# femto-beacon-esp32coin.net
KiCad netlist of a schematic drawn in EAGLE
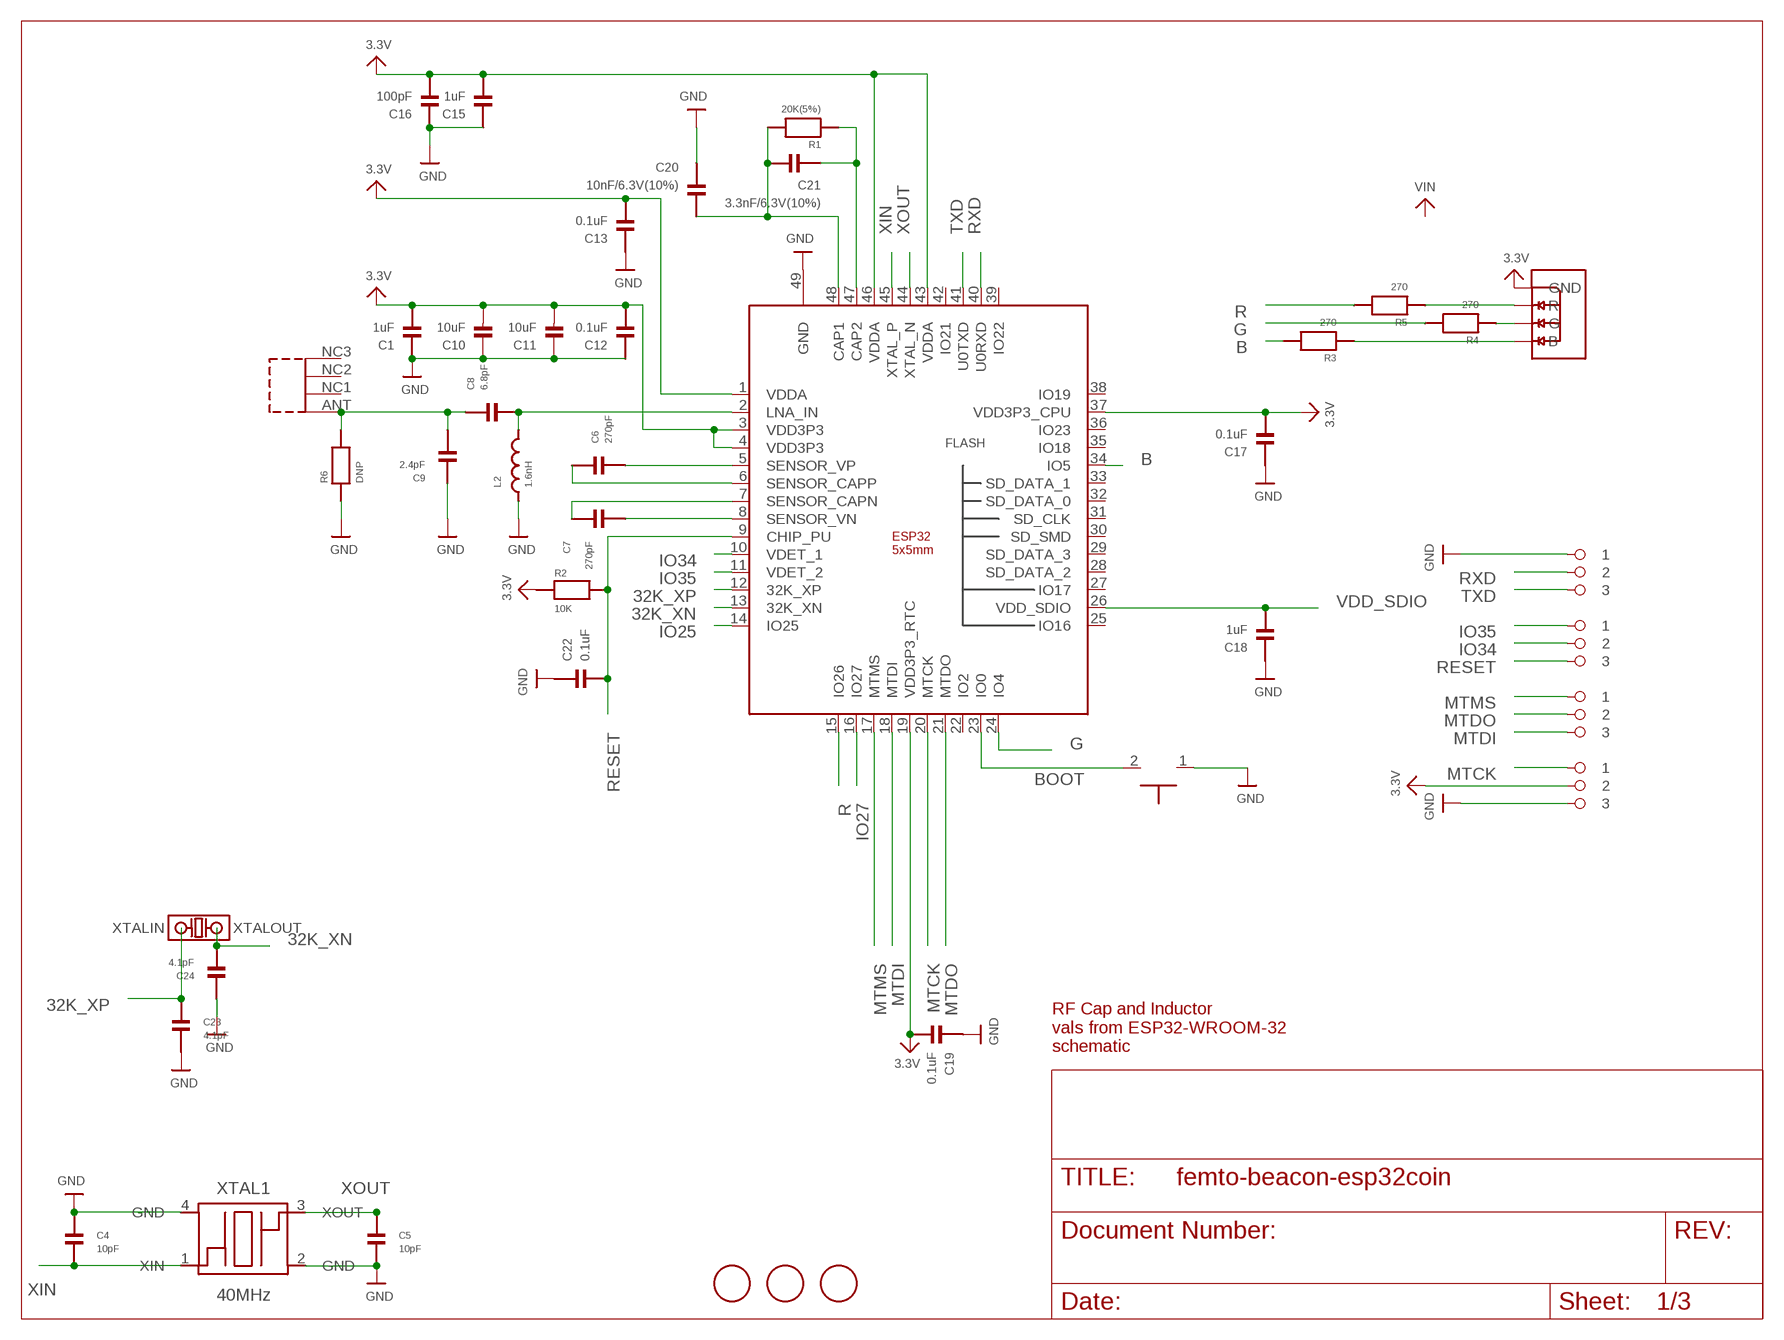
[diagram p0: schematic, sheet 1]
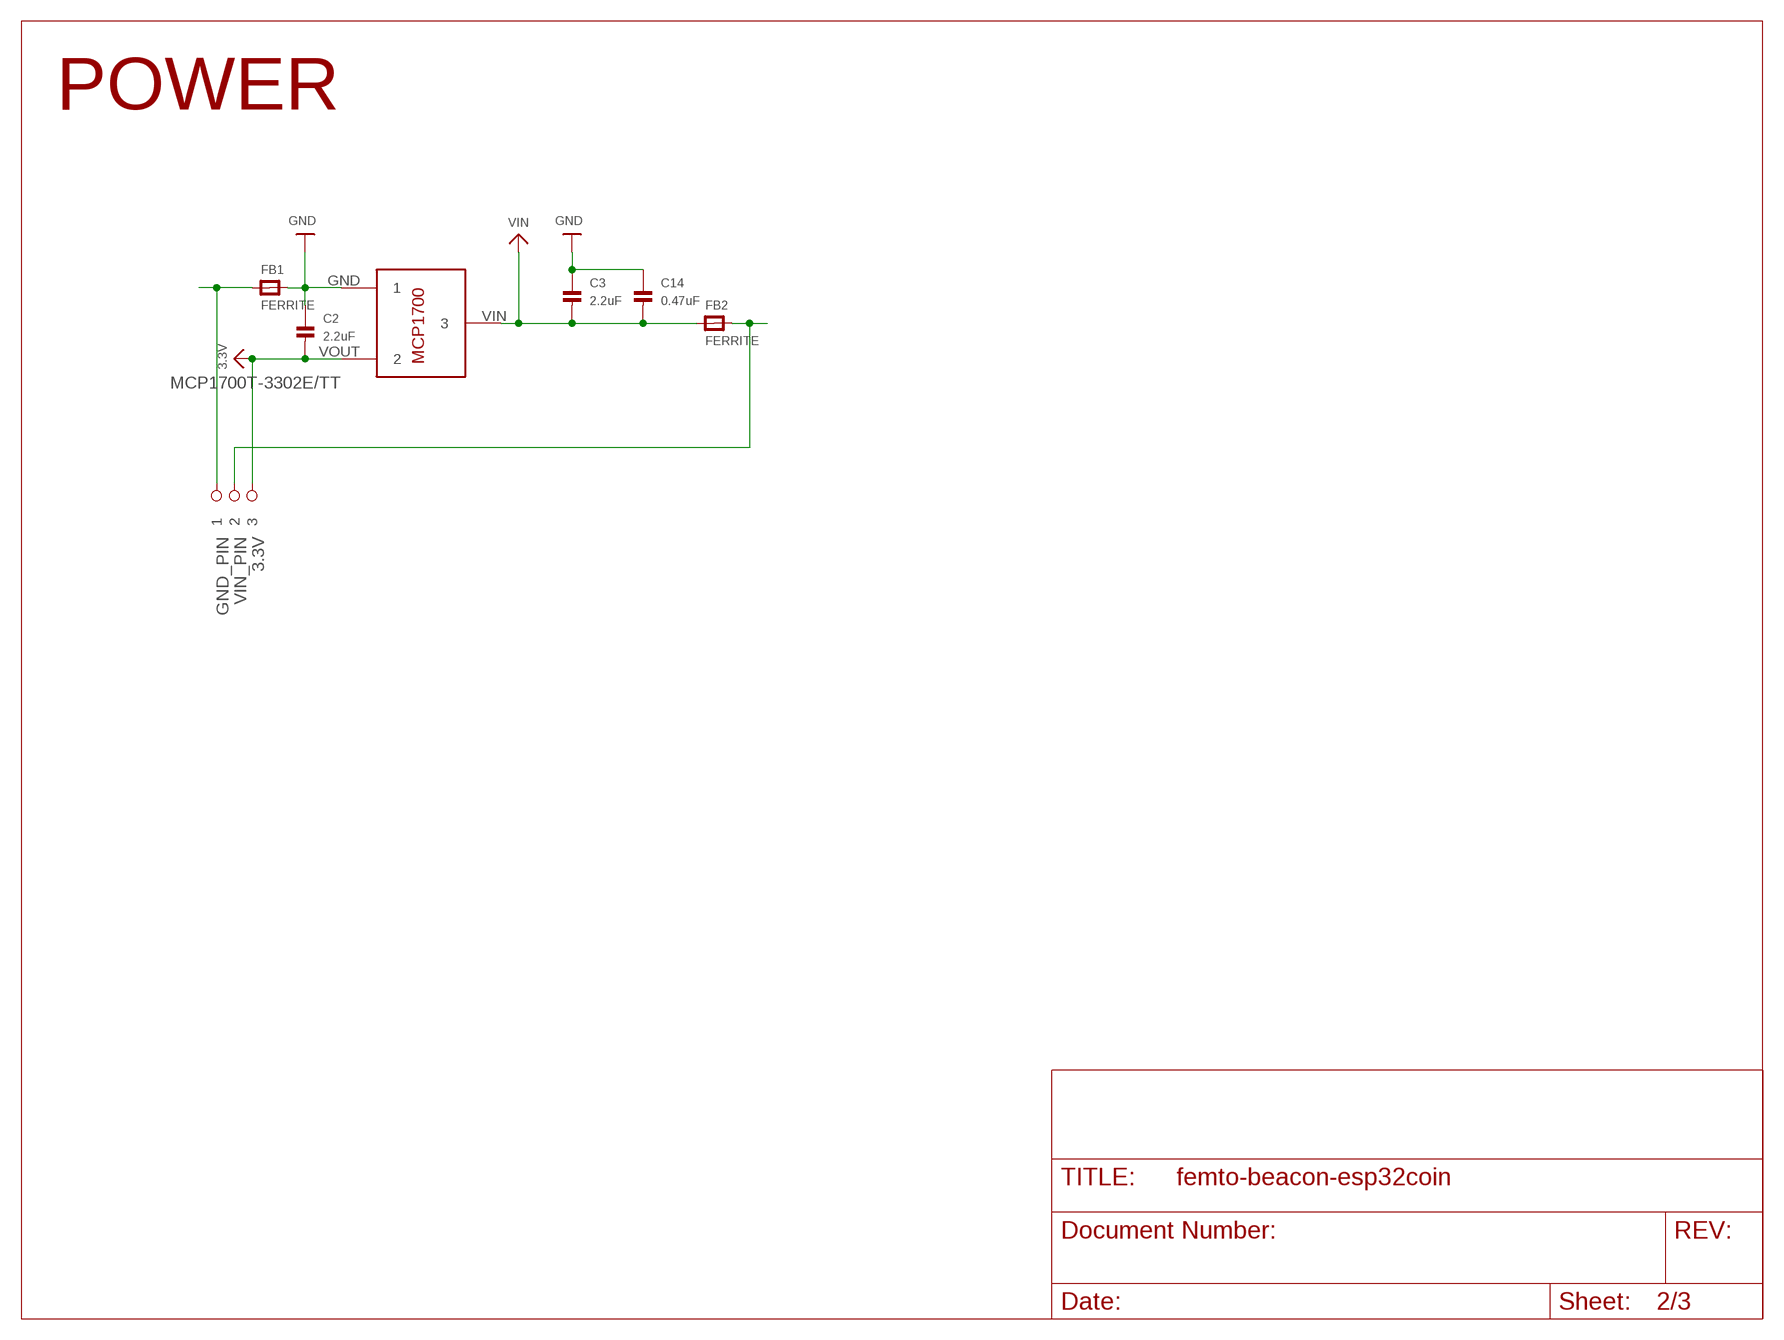
[diagram p1: schematic, sheet 2]
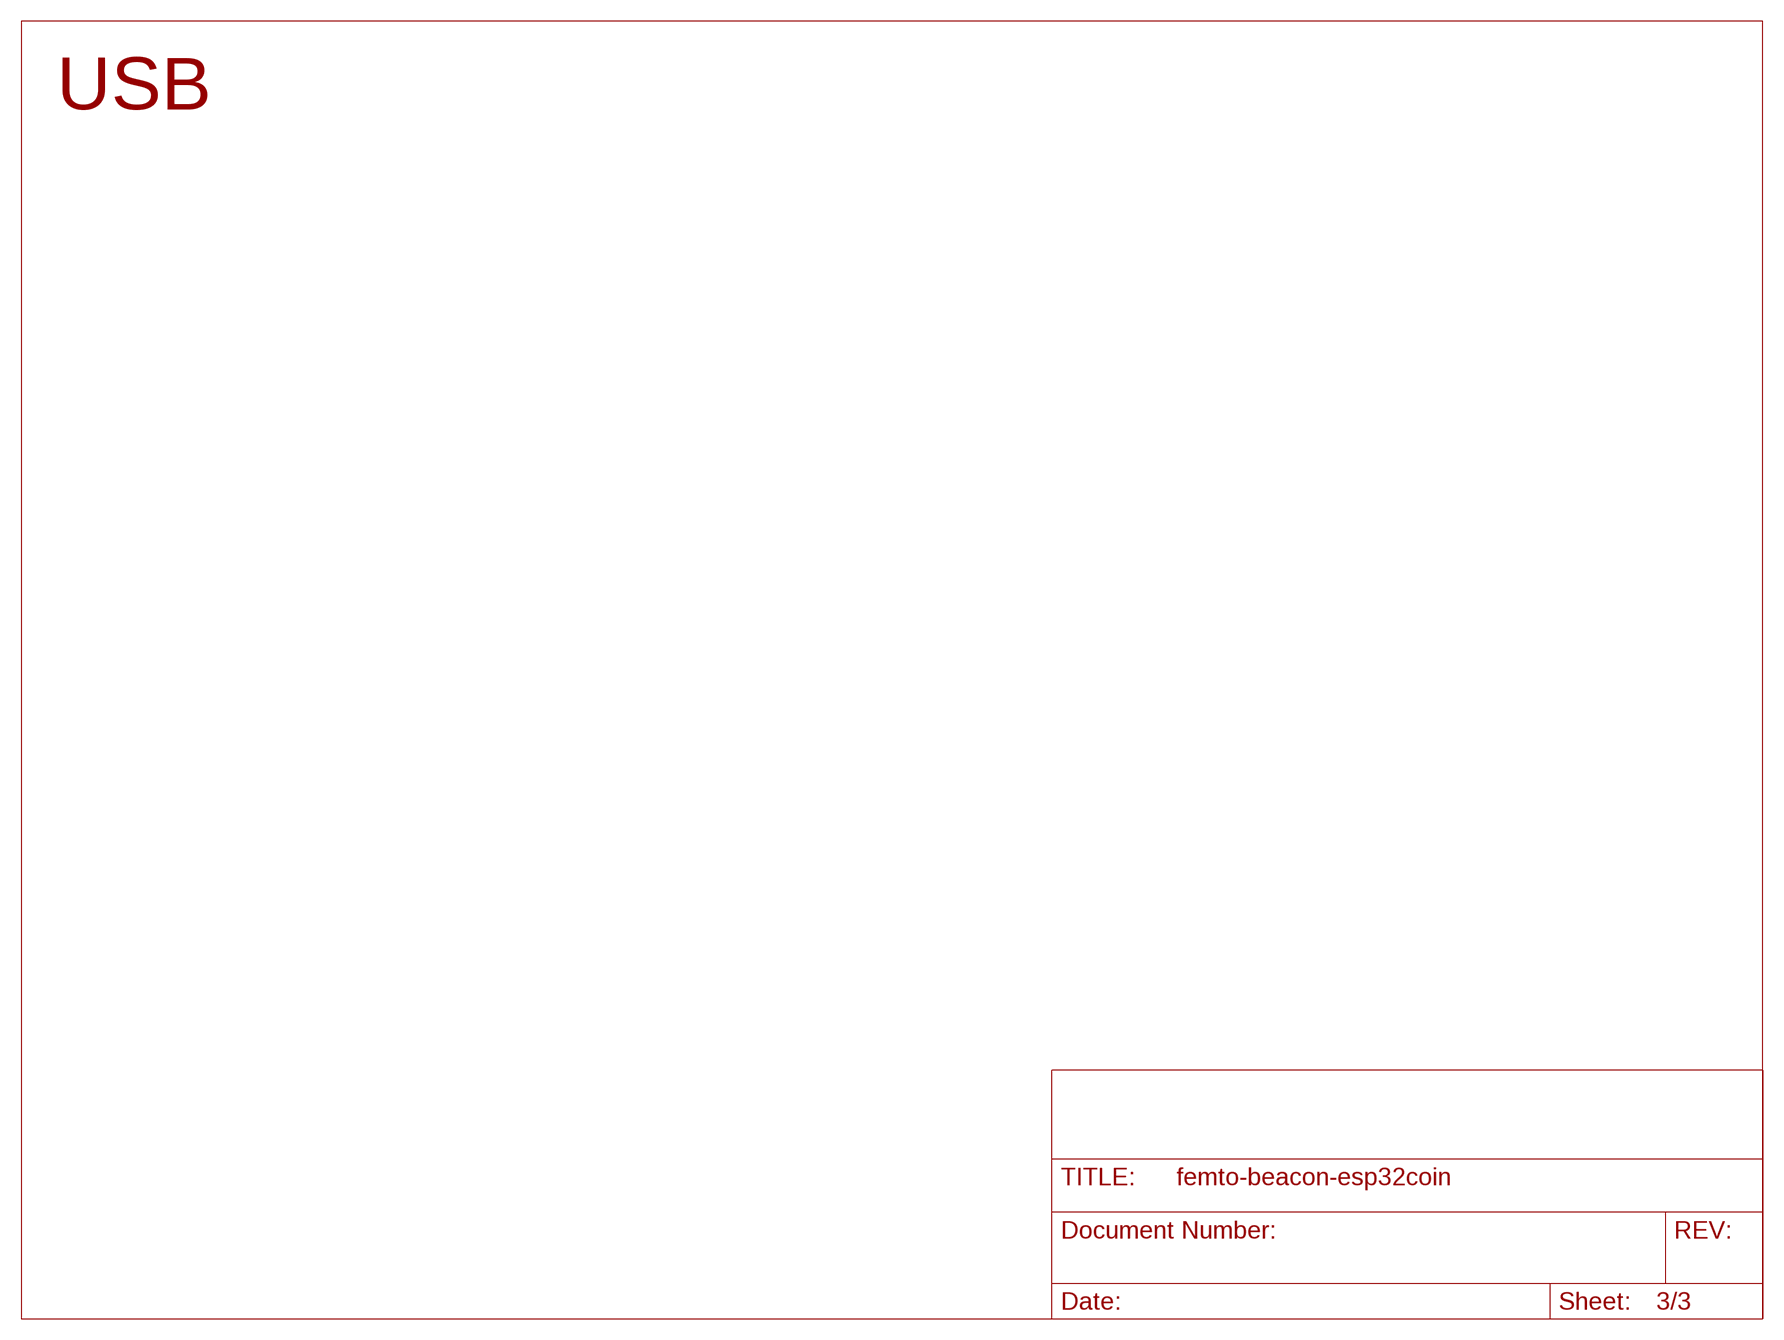
[diagram p2: schematic, sheet 3]

(export (version "E")
  (design (tool "Eeschema 10.0.6"))
  (components
    (comp (ref "C2")
      (value "2.2uF")
      (footprint "eagle-import:_0402MP")
      (fields (field (name "MPN") "C1005X5R0J225K050BC"))
      (libsource (lib "eagle-import") (part "CAP_CERAMIC_0402MP"))
    )
    (comp (ref "C3")
      (value "2.2uF")
      (footprint "eagle-import:_0402MP")
      (fields (field (name "MPN") "C1005X5R0J225K050BC"))
      (libsource (lib "eagle-import") (part "CAP_CERAMIC_0402MP"))
    )
    (comp (ref "C14")
      (value "0.47uF")
      (footprint "eagle-import:_0402MP")
      (fields (field (name "MPN") "GRM155R60J474KE19D"))
      (libsource (lib "eagle-import") (part "CAP_CERAMIC_0402MP"))
    )
    (comp (ref "FB1")
      (value "FERRITE")
      (footprint "eagle-import:_0603MP")
      (fields (field (name "MPN") "BLM18RK102SN1D"))
      (libsource (lib "eagle-import") (part "FERRITE_0603MP"))
    )
    (comp (ref "FB2")
      (value "FERRITE")
      (footprint "eagle-import:_0603MP")
      (fields (field (name "MPN") "BLM18RK102SN1D"))
      (libsource (lib "eagle-import") (part "FERRITE_0603MP"))
    )
    (comp (ref "LDO1")
      (value "MCP1700T-3302E/TT")
      (footprint "eagle-import:MCP1700T-3302E_TT")
      (libsource (lib "eagle-import") (part "MCP1700T-3302E/TT"))
    )
    (comp (ref "PIN_PWR")
      (value "1X3_ROUND")
      (footprint "eagle-import:1X3_ROUND")
      (libsource (lib "eagle-import") (part "1X3_ROUND"))
    )
    (comp (ref "ANT1")
      (value "0479480001")
      (footprint "eagle-import:0479480001")
      (libsource (lib "eagle-import") (part "0479480001"))
    )
    (comp (ref "BOOT1")
      (value "TACTILE_SWITCH_NO_GND_NO_BOSS")
      (footprint "eagle-import:SIDE_ACT_NO_GND_NO_BOSS")
      (fields (field (name "MPN") "B3U-3000P"))
      (libsource (lib "eagle-import") (part "TACTILE_SWITCH_NO_GND_NO_BOSS"))
    )
    (comp (ref "C1")
      (value "1uF")
      (footprint "eagle-import:PART")
      (fields (field (name "MPN") "CL03A105KQ3CSNH"))
      (libsource (lib "eagle-import") (part "CAPACITOR_0201"))
    )
    (comp (ref "C4")
      (value "10pF")
      (footprint "eagle-import:PART")
      (fields (field (name "MPN") "02013A100JAT2A"))
      (libsource (lib "eagle-import") (part "CAPACITOR_0201"))
    )
    (comp (ref "C5")
      (value "10pF")
      (footprint "eagle-import:PART")
      (fields (field (name "MPN") "02013A100JAT2A"))
      (libsource (lib "eagle-import") (part "CAPACITOR_0201"))
    )
    (comp (ref "C6")
      (value "270pF")
      (footprint "eagle-import:PART")
      (fields (field (name "MPN") "GRM033R71C271KA01D"))
      (libsource (lib "eagle-import") (part "CAPACITOR_0201"))
    )
    (comp (ref "C7")
      (value "270pF")
      (footprint "eagle-import:PART")
      (fields (field (name "MPN") "GRM033R71C271KA01D"))
      (libsource (lib "eagle-import") (part "CAPACITOR_0201"))
    )
    (comp (ref "C8")
      (value "6.8pF")
      (footprint "eagle-import:PART")
      (fields (field (name "MPN") "GRM0335C2A6R8DA01D"))
      (libsource (lib "eagle-import") (part "CAPACITOR_0201"))
    )
    (comp (ref "C9")
      (value "2.4pF")
      (footprint "eagle-import:PART")
      (fields (field (name "MPN") "GRM0335C1H2R4CA01D"))
      (libsource (lib "eagle-import") (part "CAPACITOR_0201"))
    )
    (comp (ref "C10")
      (value "10uF")
      (footprint "eagle-import:_0603MP")
      (fields (field (name "MPN") "GRM188R61C106KAALD"))
      (libsource (lib "eagle-import") (part "CAP_CERAMIC_0603MP"))
    )
    (comp (ref "C11")
      (value "10uF")
      (footprint "eagle-import:_0603MP")
      (fields (field (name "MPN") "GRM188R61C106KAALD"))
      (libsource (lib "eagle-import") (part "CAP_CERAMIC_0603MP"))
    )
    (comp (ref "C12")
      (value "0.1uF")
      (footprint "eagle-import:PART")
      (fields (field (name "MPN") "GRM033C80J104KE84D"))
      (libsource (lib "eagle-import") (part "CAPACITOR_0201"))
    )
    (comp (ref "C13")
      (value "0.1uF")
      (footprint "eagle-import:PART")
      (fields (field (name "MPN") "GRM033C80J104KE84D"))
      (libsource (lib "eagle-import") (part "CAPACITOR_0201"))
    )
    (comp (ref "C15")
      (value "1uF")
      (footprint "eagle-import:PART")
      (fields (field (name "MPN") "CL03A105KQ3CSNH"))
      (libsource (lib "eagle-import") (part "CAPACITOR_0201"))
    )
    (comp (ref "C16")
      (value "100pF")
      (footprint "eagle-import:PART")
      (fields (field (name "MPN") "0201YC101KAT2A"))
      (libsource (lib "eagle-import") (part "CAPACITOR_0201"))
    )
    (comp (ref "C17")
      (value "0.1uF")
      (footprint "eagle-import:PART")
      (fields (field (name "MPN") "GRM033C80J104KE84D"))
      (libsource (lib "eagle-import") (part "CAPACITOR_0201"))
    )
    (comp (ref "C18")
      (value "1uF")
      (footprint "eagle-import:PART")
      (fields (field (name "MPN") "CL03A105KQ3CSNH"))
      (libsource (lib "eagle-import") (part "CAPACITOR_0201"))
    )
    (comp (ref "C19")
      (value "0.1uF")
      (footprint "eagle-import:PART")
      (fields (field (name "MPN") "GRM033C80J104KE84D"))
      (libsource (lib "eagle-import") (part "CAPACITOR_0201"))
    )
    (comp (ref "C20")
      (value "10nF/6.3V(10%)")
      (footprint "eagle-import:PART")
      (fields (field (name "MPN") "GRM033R70J103KA01D"))
      (libsource (lib "eagle-import") (part "CAPACITOR_0201"))
    )
    (comp (ref "C21")
      (value "3.3nF/6.3V(10%)")
      (footprint "eagle-import:PART")
      (fields (field (name "MPN") "GRM033R70J332KA01D"))
      (libsource (lib "eagle-import") (part "CAPACITOR_0201"))
    )
    (comp (ref "C22")
      (value "0.1uF")
      (footprint "eagle-import:PART")
      (fields (field (name "MPN") "GRM033C80J104KE84D"))
      (libsource (lib "eagle-import") (part "CAPACITOR_0201"))
    )
    (comp (ref "C23")
      (value "4.1pF")
      (footprint "eagle-import:PART")
      (fields (field (name "MPN") "GRM0335C1H4R1BA01D"))
      (libsource (lib "eagle-import") (part "CAPACITOR_0201"))
    )
    (comp (ref "C24")
      (value "4.1pF")
      (footprint "eagle-import:PART")
      (fields (field (name "MPN") "GRM0335C1H4R1BA01D"))
      (libsource (lib "eagle-import") (part "CAPACITOR_0201"))
    )
    (comp (ref "FID1")
      (value "FIDUCIAL")
      (footprint "eagle-import:FIDUCIAL_1MM")
      (libsource (lib "eagle-import") (part "FIDUCIAL"))
    )
    (comp (ref "FID2")
      (value "FIDUCIAL")
      (footprint "eagle-import:FIDUCIAL_1MM")
      (libsource (lib "eagle-import") (part "FIDUCIAL"))
    )
    (comp (ref "FID3")
      (value "FIDUCIAL")
      (footprint "eagle-import:FIDUCIAL_1MM")
      (libsource (lib "eagle-import") (part "FIDUCIAL"))
    )
    (comp (ref "IC1")
      (value "ESP32-QFN_5X5")
      (footprint "eagle-import:ESP32-QFN48_5X5")
      (fields (field (name "MPN") "ESP32-D2WD"))
      (libsource (lib "eagle-import") (part "ESP32-QFN_5X5"))
    )
    (comp (ref "L2")
      (value "1.6nH")
      (footprint "eagle-import:PART")
      (fields (field (name "MPN") "LQP03HQ1N6B02D"))
      (libsource (lib "eagle-import") (part "INDUCTOR_FIXED_0201"))
    )
    (comp (ref "PIN_EN")
      (value "1X3_ROUND")
      (footprint "eagle-import:1X3_ROUND")
      (libsource (lib "eagle-import") (part "1X3_ROUND"))
    )
    (comp (ref "PIN_GPIO_A")
      (value "1X3_ROUND")
      (footprint "eagle-import:1X3_ROUND")
      (libsource (lib "eagle-import") (part "1X3_ROUND"))
    )
    (comp (ref "PIN_GPIO_B")
      (value "1X3_ROUND")
      (footprint "eagle-import:1X3_ROUND")
      (libsource (lib "eagle-import") (part "1X3_ROUND"))
    )
    (comp (ref "PIN_UART")
      (value "1X3_ROUND")
      (footprint "eagle-import:1X3_ROUND")
      (libsource (lib "eagle-import") (part "1X3_ROUND"))
    )
    (comp (ref "R1")
      (value "20K(5%)")
      (footprint "eagle-import:PART")
      (fields (field (name "MPN") "RC0201JR-0720KL"))
      (libsource (lib "eagle-import") (part "RESISTOR_0201"))
    )
    (comp (ref "R2")
      (value "10K")
      (footprint "eagle-import:PART")
      (fields (field (name "MPN") "RC0201JR-0710KL"))
      (libsource (lib "eagle-import") (part "RESISTOR_0201"))
    )
    (comp (ref "R3")
      (value "270")
      (footprint "eagle-import:PART")
      (fields (field (name "MPN") "RC0201FR-07270RL"))
      (libsource (lib "eagle-import") (part "RESISTOR_0201"))
    )
    (comp (ref "R4")
      (value "270")
      (footprint "eagle-import:PART")
      (fields (field (name "MPN") "RC0201FR-07270RL"))
      (libsource (lib "eagle-import") (part "RESISTOR_0201"))
    )
    (comp (ref "R5")
      (value "270")
      (footprint "eagle-import:PART")
      (fields (field (name "MPN") "RC0201FR-07270RL"))
      (libsource (lib "eagle-import") (part "RESISTOR_0201"))
    )
    (comp (ref "R6")
      (value "DNP")
      (footprint "eagle-import:PART")
      (libsource (lib "eagle-import") (part "RESISTOR_0201"))
    )
    (comp (ref "RGB1")
      (value "LRTB_R48G")
      (footprint "eagle-import:LRTB_R48G")
      (fields (field (name "MPN") "LRTB R48G"))
      (libsource (lib "eagle-import") (part "LRTB_R48G"))
    )
    (comp (ref "XTAL1")
      (value "40MHz")
      (footprint "eagle-import:FA-128")
      (fields (field (name "MPN") "FA-128 40.0000MF10Z-K3"))
      (libsource (lib "eagle-import") (part "FA-128"))
    )
    (comp (ref "XTAL2")
      (value "ABS06-107-32.768KHZ-T")
      (footprint "eagle-import:ABS06-107-32.768KHZ-T")
      (fields (field (name "MPN") "ABS06-107-32.768kHz-T"))
      (libsource (lib "eagle-import") (part "ABS06-107-32.768KHZ-T"))
    )
  )
  (nets
    (net (code "1") (name "3.3V") (class "Default")
      (node (ref "C1") (pin "2") (pinfunction "P$2_2") (pintype "bidirectional"))
      (node (ref "C10") (pin "2") (pinfunction "P$2_2") (pintype "passive"))
      (node (ref "C11") (pin "2") (pinfunction "P$2_2") (pintype "passive"))
      (node (ref "C12") (pin "2") (pinfunction "P$2_2") (pintype "bidirectional"))
      (node (ref "C13") (pin "2") (pinfunction "P$2_2") (pintype "bidirectional"))
      (node (ref "C15") (pin "2") (pinfunction "P$2_2") (pintype "bidirectional"))
      (node (ref "C16") (pin "2") (pinfunction "P$2_2") (pintype "bidirectional"))
      (node (ref "C17") (pin "2") (pinfunction "P$2_2") (pintype "bidirectional"))
      (node (ref "C19") (pin "2") (pinfunction "P$2_2") (pintype "bidirectional"))
      (node (ref "C2") (pin "2") (pinfunction "P$2_2") (pintype "passive"))
      (node (ref "IC1") (pin "1") (pinfunction "VDDA_1") (pintype "power_in"))
      (node (ref "IC1") (pin "19") (pinfunction "VDD3P3_RTC_19") (pintype "power_in"))
      (node (ref "IC1") (pin "3") (pinfunction "VDD3P3_3") (pintype "power_in"))
      (node (ref "IC1") (pin "37") (pinfunction "VDD3P3_CPU_37") (pintype "power_in"))
      (node (ref "IC1") (pin "4") (pinfunction "VDD3P3_4") (pintype "power_in"))
      (node (ref "IC1") (pin "43") (pinfunction "VDDA_43") (pintype "power_in"))
      (node (ref "IC1") (pin "46") (pinfunction "VDDA_46") (pintype "power_in"))
      (node (ref "LDO1") (pin "VOUT") (pinfunction "2_VOUT") (pintype "bidirectional"))
      (node (ref "PIN_GPIO_A") (pin "P$2") (pinfunction "2_P$2") (pintype "bidirectional"))
      (node (ref "PIN_PWR") (pin "P$3") (pinfunction "3_P$3") (pintype "bidirectional"))
      (node (ref "R2") (pin "1") (pinfunction "1_1") (pintype "bidirectional"))
      (node (ref "RGB1") (pin "1") (pinfunction "GND_1") (pintype "bidirectional"))
    )
    (net (code "2") (name "32K_XN") (class "Default")
      (node (ref "C24") (pin "1") (pinfunction "P$1_1") (pintype "bidirectional"))
      (node (ref "IC1") (pin "13") (pinfunction "32K_XN_13") (pintype "bidirectional"))
      (node (ref "XTAL2") (pin "2") (pinfunction "XTALOUT_2") (pintype "bidirectional"))
    )
    (net (code "3") (name "32K_XP") (class "Default")
      (node (ref "C23") (pin "2") (pinfunction "P$2_2") (pintype "bidirectional"))
      (node (ref "IC1") (pin "12") (pinfunction "32K_XP_12") (pintype "bidirectional"))
      (node (ref "XTAL2") (pin "1") (pinfunction "XTALIN_1") (pintype "bidirectional"))
    )
    (net (code "4") (name "B") (class "Default")
      (node (ref "IC1") (pin "34") (pinfunction "IO5_34") (pintype "bidirectional"))
      (node (ref "R3") (pin "2") (pinfunction "2_2") (pintype "bidirectional"))
    )
    (net (code "5") (name "BOOT") (class "Default")
      (node (ref "BOOT1") (pin "2") (pinfunction "2_2") (pintype "bidirectional"))
      (node (ref "IC1") (pin "23") (pinfunction "IO0_23") (pintype "bidirectional"))
    )
    (net (code "6") (name "G") (class "Default")
      (node (ref "IC1") (pin "24") (pinfunction "IO4_24") (pintype "bidirectional"))
      (node (ref "R4") (pin "2") (pinfunction "2_2") (pintype "bidirectional"))
    )
    (net (code "7") (name "GND") (class "Default")
      (node (ref "BOOT1") (pin "1") (pinfunction "1_1") (pintype "bidirectional"))
      (node (ref "C1") (pin "1") (pinfunction "P$1_1") (pintype "bidirectional"))
      (node (ref "C10") (pin "1") (pinfunction "P$1_1") (pintype "passive"))
      (node (ref "C11") (pin "1") (pinfunction "P$1_1") (pintype "passive"))
      (node (ref "C12") (pin "1") (pinfunction "P$1_1") (pintype "bidirectional"))
      (node (ref "C13") (pin "1") (pinfunction "P$1_1") (pintype "bidirectional"))
      (node (ref "C14") (pin "1") (pinfunction "P$1_1") (pintype "passive"))
      (node (ref "C15") (pin "1") (pinfunction "P$1_1") (pintype "bidirectional"))
      (node (ref "C16") (pin "1") (pinfunction "P$1_1") (pintype "bidirectional"))
      (node (ref "C17") (pin "1") (pinfunction "P$1_1") (pintype "bidirectional"))
      (node (ref "C18") (pin "1") (pinfunction "P$1_1") (pintype "bidirectional"))
      (node (ref "C19") (pin "1") (pinfunction "P$1_1") (pintype "bidirectional"))
      (node (ref "C2") (pin "1") (pinfunction "P$1_1") (pintype "passive"))
      (node (ref "C20") (pin "1") (pinfunction "P$1_1") (pintype "bidirectional"))
      (node (ref "C22") (pin "1") (pinfunction "P$1_1") (pintype "bidirectional"))
      (node (ref "C23") (pin "1") (pinfunction "P$1_1") (pintype "bidirectional"))
      (node (ref "C24") (pin "2") (pinfunction "P$2_2") (pintype "bidirectional"))
      (node (ref "C3") (pin "1") (pinfunction "P$1_1") (pintype "passive"))
      (node (ref "C4") (pin "1") (pinfunction "P$1_1") (pintype "bidirectional"))
      (node (ref "C5") (pin "1") (pinfunction "P$1_1") (pintype "bidirectional"))
      (node (ref "C9") (pin "1") (pinfunction "P$1_1") (pintype "bidirectional"))
      (node (ref "FB1") (pin "2") (pinfunction "P$2_2") (pintype "passive"))
      (node (ref "IC1") (pin "49") (pinfunction "GND_49") (pintype "power_in"))
      (node (ref "L2") (pin "1") (pinfunction "P$1_1") (pintype "bidirectional"))
      (node (ref "LDO1") (pin "GND") (pinfunction "1_GND") (pintype "bidirectional"))
      (node (ref "PIN_GPIO_A") (pin "P$3") (pinfunction "3_P$3") (pintype "bidirectional"))
      (node (ref "PIN_UART") (pin "P$1") (pinfunction "1_P$1") (pintype "bidirectional"))
      (node (ref "R6") (pin "1") (pinfunction "1_1") (pintype "bidirectional"))
      (node (ref "XTAL1") (pin "2") (pinfunction "GND_2") (pintype "bidirectional"))
      (node (ref "XTAL1") (pin "4") (pinfunction "GND_4") (pintype "bidirectional"))
    )
    (net (code "8") (name "GND_PIN") (class "Default")
      (node (ref "FB1") (pin "1") (pinfunction "P$1_1") (pintype "passive"))
      (node (ref "PIN_PWR") (pin "P$1") (pinfunction "1_P$1") (pintype "bidirectional"))
    )
    (net (code "9") (name "IO25") (class "Default")
      (node (ref "IC1") (pin "14") (pinfunction "IO25_14") (pintype "bidirectional"))
    )
    (net (code "10") (name "IO27") (class "Default")
      (node (ref "IC1") (pin "16") (pinfunction "IO27_16") (pintype "bidirectional"))
    )
    (net (code "11") (name "IO34") (class "Default")
      (node (ref "IC1") (pin "10") (pinfunction "VDET_1_10") (pintype "input"))
      (node (ref "PIN_EN") (pin "P$2") (pinfunction "2_P$2") (pintype "bidirectional"))
    )
    (net (code "12") (name "IO35") (class "Default")
      (node (ref "IC1") (pin "11") (pinfunction "VDET_2_11") (pintype "input"))
      (node (ref "PIN_EN") (pin "P$1") (pinfunction "1_P$1") (pintype "bidirectional"))
    )
    (net (code "13") (name "MTCK") (class "Default")
      (node (ref "IC1") (pin "20") (pinfunction "MTCK_20") (pintype "bidirectional"))
      (node (ref "PIN_GPIO_A") (pin "P$1") (pinfunction "1_P$1") (pintype "bidirectional"))
    )
    (net (code "14") (name "MTDI") (class "Default")
      (node (ref "IC1") (pin "18") (pinfunction "MTDI_18") (pintype "bidirectional"))
      (node (ref "PIN_GPIO_B") (pin "P$3") (pinfunction "3_P$3") (pintype "bidirectional"))
    )
    (net (code "15") (name "MTDO") (class "Default")
      (node (ref "IC1") (pin "21") (pinfunction "MTDO_21") (pintype "bidirectional"))
      (node (ref "PIN_GPIO_B") (pin "P$2") (pinfunction "2_P$2") (pintype "bidirectional"))
    )
    (net (code "16") (name "MTMS") (class "Default")
      (node (ref "IC1") (pin "17") (pinfunction "MTMS_17") (pintype "bidirectional"))
      (node (ref "PIN_GPIO_B") (pin "P$1") (pinfunction "1_P$1") (pintype "bidirectional"))
    )
    (net (code "17") (name "Net-(ANT1-1)") (class "Default")
      (node (ref "ANT1") (pin "ANT") (pinfunction "1_ANT") (pintype "bidirectional"))
      (node (ref "C8") (pin "1") (pinfunction "P$1_1") (pintype "bidirectional"))
      (node (ref "C9") (pin "2") (pinfunction "P$2_2") (pintype "bidirectional"))
      (node (ref "R6") (pin "2") (pinfunction "2_2") (pintype "bidirectional"))
    )
    (net (code "18") (name "Net-(C6-P$1)") (class "Default")
      (node (ref "C6") (pin "1") (pinfunction "P$1_1") (pintype "bidirectional"))
      (node (ref "IC1") (pin "5") (pinfunction "SENSOR_VP_5") (pintype "input"))
    )
    (net (code "19") (name "Net-(C6-P$2)") (class "Default")
      (node (ref "C6") (pin "2") (pinfunction "P$2_2") (pintype "bidirectional"))
      (node (ref "IC1") (pin "6") (pinfunction "SENSOR_CAPP_6") (pintype "input"))
    )
    (net (code "20") (name "Net-(C7-P$1)") (class "Default")
      (node (ref "C7") (pin "1") (pinfunction "P$1_1") (pintype "bidirectional"))
      (node (ref "IC1") (pin "7") (pinfunction "SENSOR_CAPN_7") (pintype "input"))
    )
    (net (code "21") (name "Net-(C7-P$2)") (class "Default")
      (node (ref "C7") (pin "2") (pinfunction "P$2_2") (pintype "bidirectional"))
      (node (ref "IC1") (pin "8") (pinfunction "SENSOR_VN_8") (pintype "input"))
    )
    (net (code "22") (name "Net-(C8-P$2)") (class "Default")
      (node (ref "C8") (pin "2") (pinfunction "P$2_2") (pintype "bidirectional"))
      (node (ref "IC1") (pin "2") (pinfunction "LNA_IN_2") (pintype "bidirectional"))
      (node (ref "L2") (pin "2") (pinfunction "P$2_2") (pintype "bidirectional"))
    )
    (net (code "23") (name "Net-(C20-P$2)") (class "Default")
      (node (ref "C20") (pin "2") (pinfunction "P$2_2") (pintype "bidirectional"))
      (node (ref "C21") (pin "1") (pinfunction "P$1_1") (pintype "bidirectional"))
      (node (ref "IC1") (pin "48") (pinfunction "CAP1_48") (pintype "input"))
      (node (ref "R1") (pin "2") (pinfunction "2_2") (pintype "bidirectional"))
    )
    (net (code "24") (name "Net-(C21-P$2)") (class "Default")
      (node (ref "C21") (pin "2") (pinfunction "P$2_2") (pintype "bidirectional"))
      (node (ref "IC1") (pin "47") (pinfunction "CAP2_47") (pintype "input"))
      (node (ref "R1") (pin "1") (pinfunction "1_1") (pintype "bidirectional"))
    )
    (net (code "25") (name "Net-(RGB1-B)") (class "Default")
      (node (ref "R3") (pin "1") (pinfunction "1_1") (pintype "bidirectional"))
      (node (ref "RGB1") (pin "4") (pinfunction "B_4") (pintype "bidirectional"))
    )
    (net (code "26") (name "Net-(RGB1-G)") (class "Default")
      (node (ref "R4") (pin "1") (pinfunction "1_1") (pintype "bidirectional"))
      (node (ref "RGB1") (pin "3") (pinfunction "G_3") (pintype "bidirectional"))
    )
    (net (code "27") (name "Net-(RGB1-R)") (class "Default")
      (node (ref "R5") (pin "1") (pinfunction "1_1") (pintype "bidirectional"))
      (node (ref "RGB1") (pin "2") (pinfunction "R_2") (pintype "bidirectional"))
    )
    (net (code "28") (name "R") (class "Default")
      (node (ref "IC1") (pin "15") (pinfunction "IO26_15") (pintype "bidirectional"))
      (node (ref "R5") (pin "2") (pinfunction "2_2") (pintype "bidirectional"))
    )
    (net (code "29") (name "RESET") (class "Default")
      (node (ref "C22") (pin "2") (pinfunction "P$2_2") (pintype "bidirectional"))
      (node (ref "IC1") (pin "9") (pinfunction "CHIP_PU_9") (pintype "input"))
      (node (ref "PIN_EN") (pin "P$3") (pinfunction "3_P$3") (pintype "bidirectional"))
      (node (ref "R2") (pin "2") (pinfunction "2_2") (pintype "bidirectional"))
    )
    (net (code "30") (name "RXD") (class "Default")
      (node (ref "IC1") (pin "40") (pinfunction "U0RXD_40") (pintype "bidirectional"))
      (node (ref "PIN_UART") (pin "P$2") (pinfunction "2_P$2") (pintype "bidirectional"))
    )
    (net (code "31") (name "TXD") (class "Default")
      (node (ref "IC1") (pin "41") (pinfunction "U0TXD_41") (pintype "bidirectional"))
      (node (ref "PIN_UART") (pin "P$3") (pinfunction "3_P$3") (pintype "bidirectional"))
    )
    (net (code "32") (name "VDD_SDIO") (class "Default")
      (node (ref "C18") (pin "2") (pinfunction "P$2_2") (pintype "bidirectional"))
      (node (ref "IC1") (pin "26") (pinfunction "VDD_SDIO_26") (pintype "power_in"))
    )
    (net (code "33") (name "VIN") (class "Default")
      (node (ref "C14") (pin "2") (pinfunction "P$2_2") (pintype "passive"))
      (node (ref "C3") (pin "2") (pinfunction "P$2_2") (pintype "passive"))
      (node (ref "FB2") (pin "1") (pinfunction "P$1_1") (pintype "passive"))
      (node (ref "LDO1") (pin "VIN") (pinfunction "3_VIN") (pintype "bidirectional"))
    )
    (net (code "34") (name "VIN_PIN") (class "Default")
      (node (ref "FB2") (pin "2") (pinfunction "P$2_2") (pintype "passive"))
      (node (ref "PIN_PWR") (pin "P$2") (pinfunction "2_P$2") (pintype "bidirectional"))
    )
    (net (code "35") (name "XIN") (class "Default")
      (node (ref "C4") (pin "2") (pinfunction "P$2_2") (pintype "bidirectional"))
      (node (ref "IC1") (pin "45") (pinfunction "XTAL_P_45") (pintype "input"))
      (node (ref "XTAL1") (pin "1") (pinfunction "XIN_1") (pintype "bidirectional"))
    )
    (net (code "36") (name "XOUT") (class "Default")
      (node (ref "C5") (pin "2") (pinfunction "P$2_2") (pintype "bidirectional"))
      (node (ref "IC1") (pin "44") (pinfunction "XTAL_N_44") (pintype "bidirectional"))
      (node (ref "XTAL1") (pin "3") (pinfunction "XOUT_3") (pintype "bidirectional"))
    )
    (net (code "37") (name "unconnected-(ANT1-2-PadNC1)") (class "Default")
      (node (ref "ANT1") (pin "NC1") (pinfunction "2_NC1") (pintype "bidirectional"))
    )
    (net (code "38") (name "unconnected-(ANT1-3-PadNC2)") (class "Default")
      (node (ref "ANT1") (pin "NC2") (pinfunction "3_NC2") (pintype "bidirectional"))
    )
    (net (code "39") (name "unconnected-(ANT1-4-PadNC3)") (class "Default")
      (node (ref "ANT1") (pin "NC3") (pinfunction "4_NC3") (pintype "bidirectional"))
    )
    (net (code "40") (name "unconnected-(IC1-IO2-Pad22)") (class "Default")
      (node (ref "IC1") (pin "22") (pinfunction "IO2_22") (pintype "bidirectional"))
    )
    (net (code "41") (name "unconnected-(IC1-IO16-Pad25)") (class "Default")
      (node (ref "IC1") (pin "25") (pinfunction "IO16_25") (pintype "bidirectional"))
    )
    (net (code "42") (name "unconnected-(IC1-IO17-Pad27)") (class "Default")
      (node (ref "IC1") (pin "27") (pinfunction "IO17_27") (pintype "bidirectional"))
    )
    (net (code "43") (name "unconnected-(IC1-IO18-Pad35)") (class "Default")
      (node (ref "IC1") (pin "35") (pinfunction "IO18_35") (pintype "bidirectional"))
    )
    (net (code "44") (name "unconnected-(IC1-IO19-Pad38)") (class "Default")
      (node (ref "IC1") (pin "38") (pinfunction "IO19_38") (pintype "bidirectional"))
    )
    (net (code "45") (name "unconnected-(IC1-IO21-Pad42)") (class "Default")
      (node (ref "IC1") (pin "42") (pinfunction "IO21_42") (pintype "bidirectional"))
    )
    (net (code "46") (name "unconnected-(IC1-IO22-Pad39)") (class "Default")
      (node (ref "IC1") (pin "39") (pinfunction "IO22_39") (pintype "bidirectional"))
    )
    (net (code "47") (name "unconnected-(IC1-IO23-Pad36)") (class "Default")
      (node (ref "IC1") (pin "36") (pinfunction "IO23_36") (pintype "bidirectional"))
    )
    (net (code "48") (name "unconnected-(IC1-SD_CLK-Pad31)") (class "Default")
      (node (ref "IC1") (pin "31") (pinfunction "SD_CLK_31") (pintype "bidirectional"))
    )
    (net (code "49") (name "unconnected-(IC1-SD_DATA_0-Pad32)") (class "Default")
      (node (ref "IC1") (pin "32") (pinfunction "SD_DATA_0_32") (pintype "bidirectional"))
    )
    (net (code "50") (name "unconnected-(IC1-SD_DATA_1-Pad33)") (class "Default")
      (node (ref "IC1") (pin "33") (pinfunction "SD_DATA_1_33") (pintype "bidirectional"))
    )
    (net (code "51") (name "unconnected-(IC1-SD_DATA_2-Pad28)") (class "Default")
      (node (ref "IC1") (pin "28") (pinfunction "SD_DATA_2_28") (pintype "bidirectional"))
    )
    (net (code "52") (name "unconnected-(IC1-SD_DATA_3-Pad29)") (class "Default")
      (node (ref "IC1") (pin "29") (pinfunction "SD_DATA_3_29") (pintype "bidirectional"))
    )
    (net (code "53") (name "unconnected-(IC1-SD_SMD-Pad30)") (class "Default")
      (node (ref "IC1") (pin "30") (pinfunction "SD_SMD_30") (pintype "bidirectional"))
    )
  )
)
